# Connectors_1.net
KiCad netlist of a schematic drawn in Altium Designer
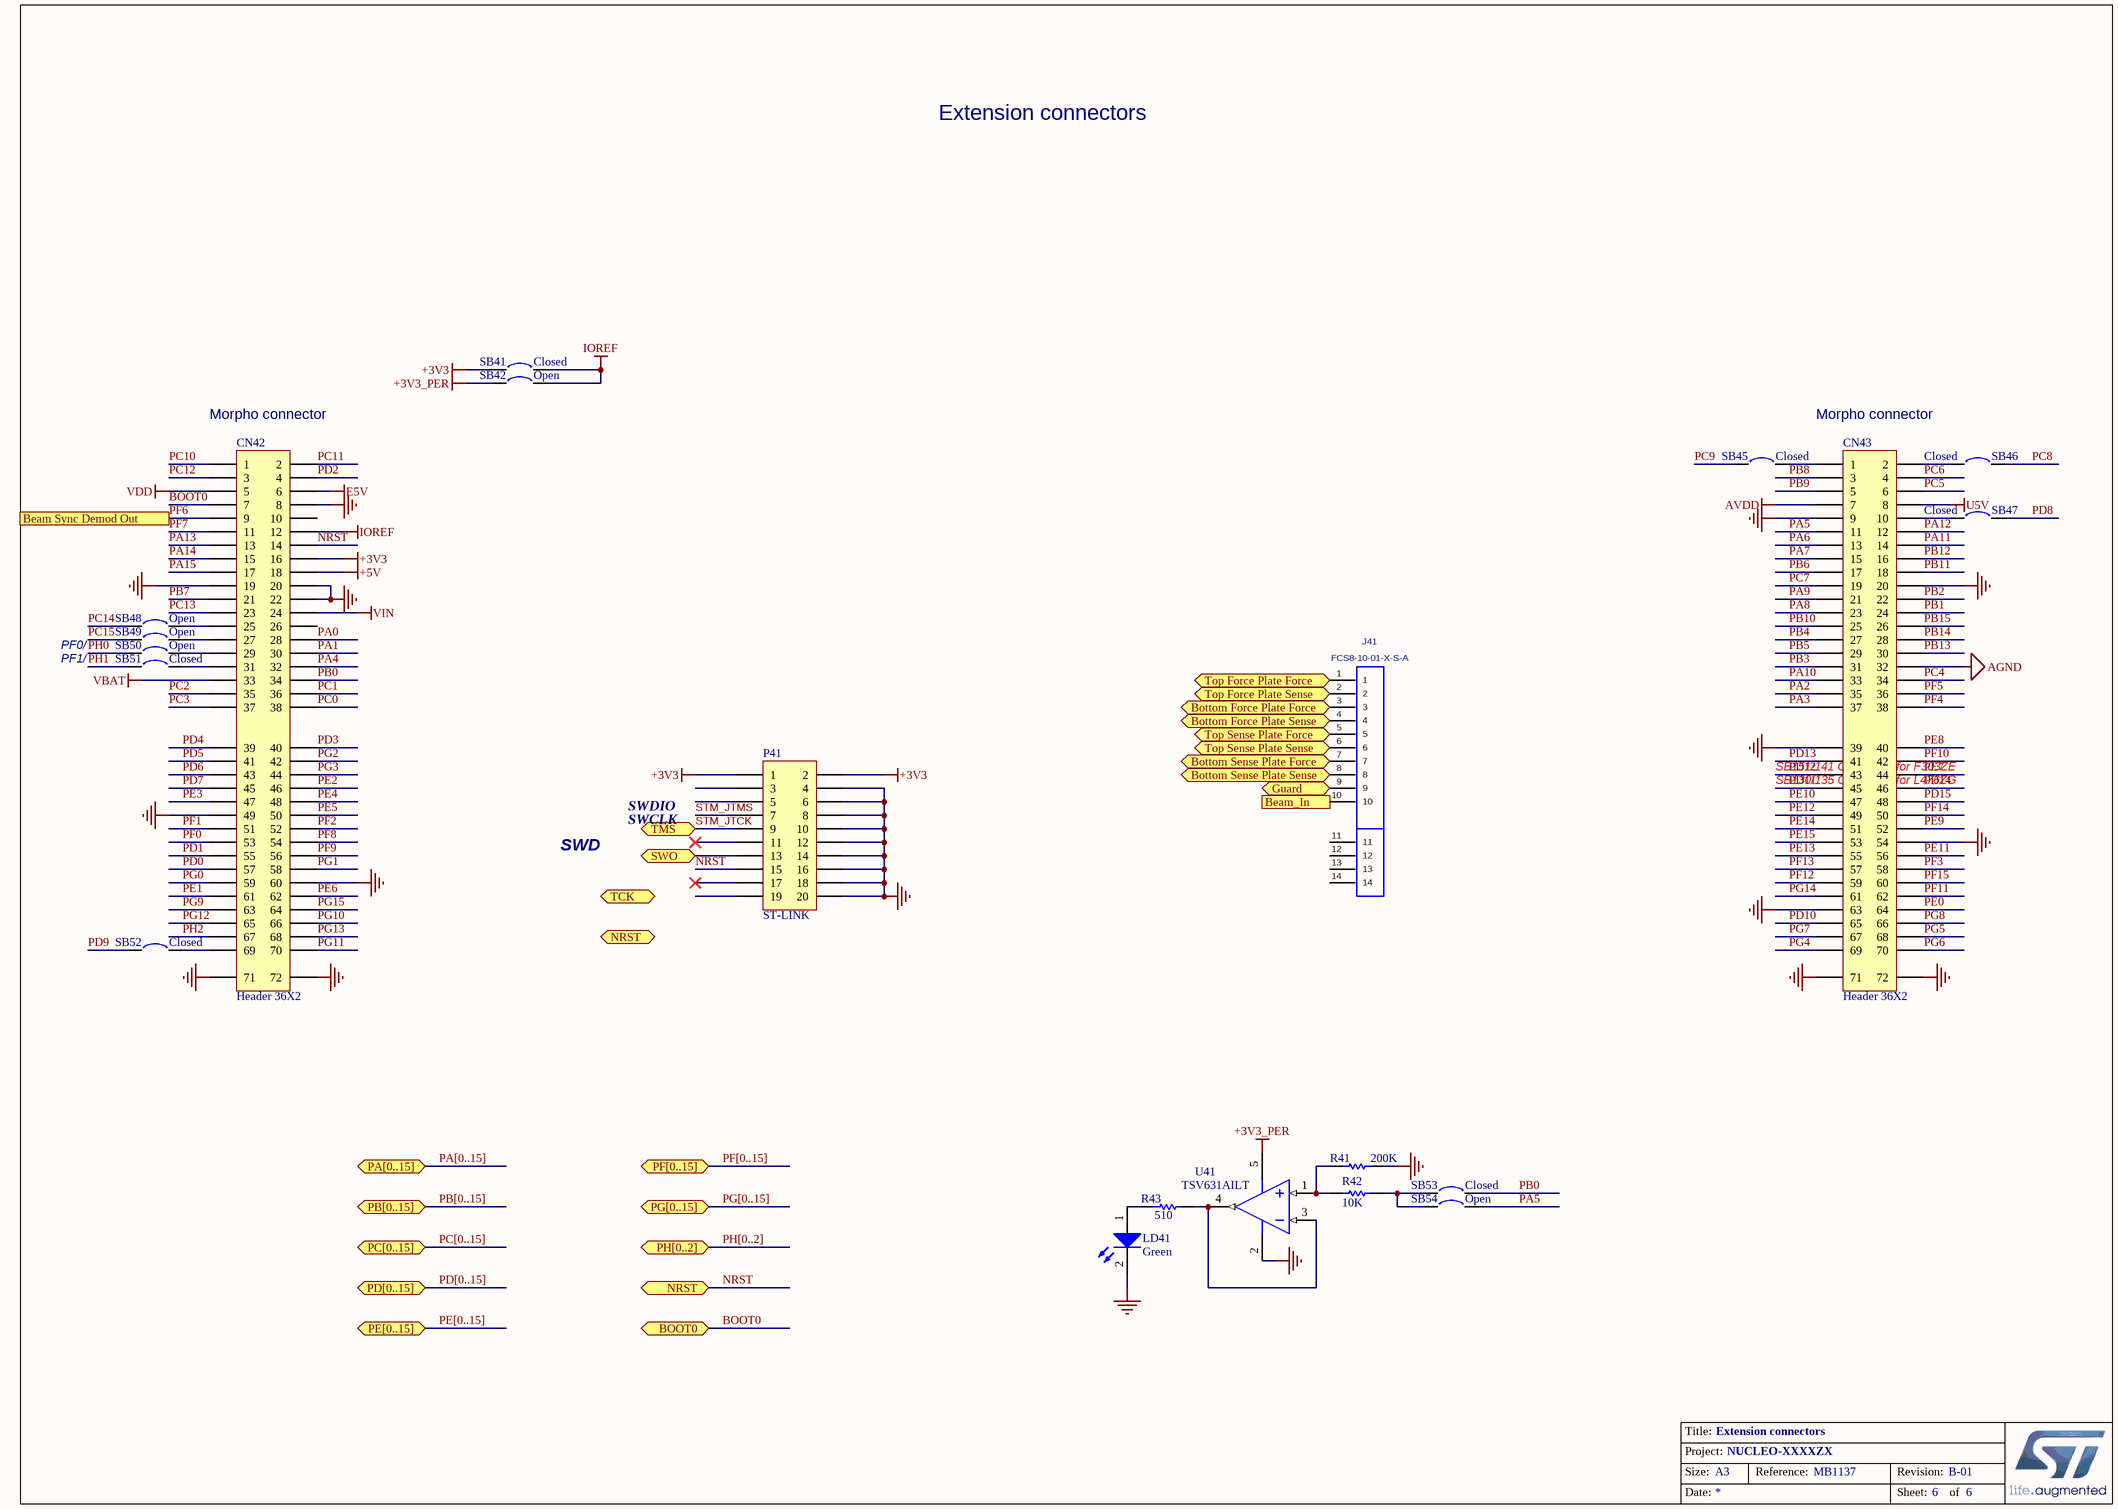
[diagram p0: Connectors_1.SchDoc]

(export (version "E")
  (design (tool "Eeschema 10.0.6"))
  (components
    (comp (ref "CN42")
      (value "Header 36X2")
      (footprint "HDR_2x36_2R54_V_M")
      (description "Header, 36-Pin, Dual row")
      (fields (field (name "PUBLISHER") "Altium Limited"))
      (libsource (lib "MB1137") (part "Header 36X2"))
    )
    (comp (ref "CN43")
      (value "Header 36X2")
      (footprint "HDR_2x36_2R54_V_M")
      (description "Header, 36-Pin, Dual row")
      (fields (field (name "PUBLISHER") "Altium Limited"))
      (libsource (lib "MB1137") (part "Header 36X2"))
    )
    (comp (ref "J41")
      (value "FCS8-10-01-X-S-A")
      (footprint "FCS8-10-01-X-S-A")
      (description "FCS8 Socket Assembly, 20-Pins, w/ Alignment Pins")
      (fields (field (name "MANUFACTURER") "SAMTEC") (field (name "CREATED") "31 NOV 2013 - WENDY XIN"))
      (libsource (lib "FCS8-10-01-X-S-A") (part "FCS8-10-01-X-S-A"))
    )
    (comp (ref "LD41")
      (value "Green")
      (footprint "0603D-G")
      (description "Typical RED, GREEN, YELLOW, AMBER GaAs LED")
      (fields (field (name "PUBLISHER") "Altium Limited"))
      (libsource (lib "Miscellaneous Devices") (part "LED2"))
    )
    (comp (ref "P41")
      (value "ST-LINK")
      (footprint "HDR2X10")
      (description "Header, 10-Pin, Dual row")
      (fields (field (name "PUBLISHER") "Altium Limited"))
      (libsource (lib "Miscellaneous Connectors") (part "Header 10X2"))
    )
    (comp (ref "R41")
      (value "200K")
      (footprint "0603R")
      (description "Resistor")
      (fields (field (name "PUBLISHER") "Altium Limited"))
      (libsource (lib "Miscellaneous Devices") (part "res1"))
    )
    (comp (ref "R42")
      (value "10K")
      (footprint "0603R")
      (description "Resistor")
      (fields (field (name "PUBLISHER") "Altium Limited"))
      (libsource (lib "Miscellaneous Devices") (part "res1"))
    )
    (comp (ref "R43")
      (value "510")
      (footprint "0603R")
      (description "Resistor")
      (fields (field (name "PUBLISHER") "Altium Limited"))
      (libsource (lib "Miscellaneous Devices") (part "Res1"))
    )
    (comp (ref "SB41")
      (value "Closed")
      (footprint "SB_0603")
      (description "Circuit Breaker")
      (fields (field (name "PUBLISHER") "Altium Limited"))
      (libsource (lib "MB1167") (part "Circuit Breaker_close"))
    )
    (comp (ref "SB42")
      (value "Open")
      (footprint "SB_0603")
      (description "Circuit Breaker")
      (fields (field (name "PUBLISHER") "Altium Limited"))
      (libsource (lib "MB1167") (part "Circuit Breaker"))
    )
    (comp (ref "SB45")
      (value "Closed")
      (footprint "SB_0603")
      (description "Circuit Breaker")
      (fields (field (name "PUBLISHER") "Altium Limited"))
      (libsource (lib "MB1167") (part "Circuit Breaker_close"))
    )
    (comp (ref "SB46")
      (value "Closed")
      (footprint "SB_0603")
      (description "Circuit Breaker")
      (fields (field (name "PUBLISHER") "Altium Limited"))
      (libsource (lib "") (part "Circuit Breaker_close_1"))
    )
    (comp (ref "SB47")
      (value "Closed")
      (footprint "SB_0603")
      (description "Circuit Breaker")
      (fields (field (name "PUBLISHER") "Altium Limited"))
      (libsource (lib "MB1167") (part "Circuit Breaker_close"))
    )
    (comp (ref "SB48")
      (value "Open")
      (footprint "SB_0603")
      (description "Circuit Breaker")
      (fields (field (name "PUBLISHER") "Altium Limited"))
      (libsource (lib "MB1167") (part "Circuit Breaker"))
    )
    (comp (ref "SB49")
      (value "Open")
      (footprint "SB_0603")
      (description "Circuit Breaker")
      (fields (field (name "PUBLISHER") "Altium Limited"))
      (libsource (lib "MB1167") (part "Circuit Breaker"))
    )
    (comp (ref "SB50")
      (value "Open")
      (footprint "SB_0603")
      (description "Circuit Breaker")
      (fields (field (name "PUBLISHER") "Altium Limited"))
      (libsource (lib "MB1167") (part "Circuit Breaker"))
    )
    (comp (ref "SB51")
      (value "Closed")
      (footprint "SB_0603")
      (description "Circuit Breaker")
      (fields (field (name "PUBLISHER") "Altium Limited"))
      (libsource (lib "MB1167") (part "Circuit Breaker_close"))
    )
    (comp (ref "SB52")
      (value "Closed")
      (footprint "SB_0603")
      (description "Circuit Breaker")
      (fields (field (name "PUBLISHER") "Altium Limited"))
      (libsource (lib "MB1167") (part "Circuit Breaker_close"))
    )
    (comp (ref "SB53")
      (value "Closed")
      (footprint "SB_0603")
      (description "Circuit Breaker")
      (fields (field (name "PUBLISHER") "Altium Limited"))
      (libsource (lib "") (part "Circuit Breaker_close_1"))
    )
    (comp (ref "SB54")
      (value "Open")
      (footprint "SB_0603")
      (description "Circuit Breaker")
      (fields (field (name "PUBLISHER") "Altium Limited"))
      (libsource (lib "MB1167") (part "Circuit Breaker"))
    )
    (comp (ref "U41")
      (value "TSV631AILT")
      (footprint "SOT-23-5L")
      (libsource (lib "MB988") (part "TSV631AILT"))
    )
  )
  (nets
    (net (code "1") (name "+3V3") (class "Default")
      (node (ref "CN42") (pin "16") (pinfunction "16_16") (pintype "passive"))
      (node (ref "P41") (pin "1") (pinfunction "1_1") (pintype "passive"))
      (node (ref "P41") (pin "2") (pinfunction "2_2") (pintype "passive"))
      (node (ref "SB41") (pin "1") (pinfunction "1_1") (pintype "passive"))
    )
    (net (code "2") (name "+3V3_PER") (class "Default")
      (node (ref "SB42") (pin "1") (pinfunction "1_1") (pintype "passive"))
      (node (ref "U41") (pin "5") (pinfunction "VCC_5") (pintype "power_in"))
    )
    (net (code "3") (name "+5V") (class "Default")
      (node (ref "CN42") (pin "18") (pinfunction "18_18") (pintype "passive"))
    )
    (net (code "4") (name "/BOOT0") (class "Default")
      (node (ref "CN42") (pin "7") (pinfunction "7_7") (pintype "passive"))
    )
    (net (code "5") (name "/Beam_In") (class "Default")
      (node (ref "J41") (pin "10") (pinfunction "10_10") (pintype "passive"))
    )
    (net (code "6") (name "/Bottom Force Plate Force") (class "Default")
      (node (ref "J41") (pin "3") (pinfunction "3_3") (pintype "passive"))
    )
    (net (code "7") (name "/Bottom Force Plate Sense") (class "Default")
      (node (ref "J41") (pin "4") (pinfunction "4_4") (pintype "passive"))
    )
    (net (code "8") (name "/Bottom Sense Plate Force") (class "Default")
      (node (ref "J41") (pin "7") (pinfunction "7_7") (pintype "passive"))
    )
    (net (code "9") (name "/Bottom Sense Plate Sense") (class "Default")
      (node (ref "J41") (pin "8") (pinfunction "8_8") (pintype "passive"))
    )
    (net (code "10") (name "/Guard") (class "Default")
      (node (ref "J41") (pin "9") (pinfunction "9_9") (pintype "passive"))
    )
    (net (code "11") (name "/NRST") (class "Default")
      (node (ref "CN42") (pin "14") (pinfunction "14_14") (pintype "passive"))
      (node (ref "P41") (pin "15") (pinfunction "15_15") (pintype "passive"))
    )
    (net (code "12") (name "/PA0") (class "Default")
      (node (ref "CN42") (pin "28") (pinfunction "28_28") (pintype "passive"))
    )
    (net (code "13") (name "/PA1") (class "Default")
      (node (ref "CN42") (pin "30") (pinfunction "30_30") (pintype "passive"))
    )
    (net (code "14") (name "/PA2") (class "Default")
      (node (ref "CN43") (pin "35") (pinfunction "35_35") (pintype "passive"))
    )
    (net (code "15") (name "/PA3") (class "Default")
      (node (ref "CN43") (pin "37") (pinfunction "37_37") (pintype "passive"))
    )
    (net (code "16") (name "/PA4") (class "Default")
      (node (ref "CN42") (pin "32") (pinfunction "32_32") (pintype "passive"))
    )
    (net (code "17") (name "/PA5") (class "Default")
      (node (ref "CN43") (pin "11") (pinfunction "11_11") (pintype "passive"))
      (node (ref "SB54") (pin "2") (pinfunction "2_2") (pintype "passive"))
    )
    (net (code "18") (name "/PA6") (class "Default")
      (node (ref "CN43") (pin "13") (pinfunction "13_13") (pintype "passive"))
    )
    (net (code "19") (name "/PA7") (class "Default")
      (node (ref "CN43") (pin "15") (pinfunction "15_15") (pintype "passive"))
    )
    (net (code "20") (name "/PA8") (class "Default")
      (node (ref "CN43") (pin "23") (pinfunction "23_23") (pintype "passive"))
    )
    (net (code "21") (name "/PA9") (class "Default")
      (node (ref "CN43") (pin "21") (pinfunction "21_21") (pintype "passive"))
    )
    (net (code "22") (name "/PA10") (class "Default")
      (node (ref "CN43") (pin "33") (pinfunction "33_33") (pintype "passive"))
    )
    (net (code "23") (name "/PA11") (class "Default")
      (node (ref "CN43") (pin "14") (pinfunction "14_14") (pintype "passive"))
    )
    (net (code "24") (name "/PA12") (class "Default")
      (node (ref "CN43") (pin "12") (pinfunction "12_12") (pintype "passive"))
    )
    (net (code "25") (name "/PA13") (class "Default")
      (node (ref "CN42") (pin "13") (pinfunction "13_13") (pintype "passive"))
    )
    (net (code "26") (name "/PA14") (class "Default")
      (node (ref "CN42") (pin "15") (pinfunction "15_15") (pintype "passive"))
    )
    (net (code "27") (name "/PA15") (class "Default")
      (node (ref "CN42") (pin "17") (pinfunction "17_17") (pintype "passive"))
    )
    (net (code "29") (name "/PB0") (class "Default")
      (node (ref "CN42") (pin "34") (pinfunction "34_34") (pintype "passive"))
      (node (ref "SB53") (pin "1") (pinfunction "1_1") (pintype "passive"))
    )
    (net (code "30") (name "/PB1") (class "Default")
      (node (ref "CN43") (pin "24") (pinfunction "24_24") (pintype "passive"))
    )
    (net (code "31") (name "/PB2") (class "Default")
      (node (ref "CN43") (pin "22") (pinfunction "22_22") (pintype "passive"))
    )
    (net (code "32") (name "/PB3") (class "Default")
      (node (ref "CN43") (pin "31") (pinfunction "31_31") (pintype "passive"))
    )
    (net (code "33") (name "/PB4") (class "Default")
      (node (ref "CN43") (pin "27") (pinfunction "27_27") (pintype "passive"))
    )
    (net (code "34") (name "/PB5") (class "Default")
      (node (ref "CN43") (pin "29") (pinfunction "29_29") (pintype "passive"))
    )
    (net (code "35") (name "/PB6") (class "Default")
      (node (ref "CN43") (pin "17") (pinfunction "17_17") (pintype "passive"))
    )
    (net (code "36") (name "/PB7") (class "Default")
      (node (ref "CN42") (pin "21") (pinfunction "21_21") (pintype "passive"))
    )
    (net (code "37") (name "/PB8") (class "Default")
      (node (ref "CN43") (pin "3") (pinfunction "3_3") (pintype "passive"))
    )
    (net (code "38") (name "/PB9") (class "Default")
      (node (ref "CN43") (pin "5") (pinfunction "5_5") (pintype "passive"))
    )
    (net (code "39") (name "/PB10") (class "Default")
      (node (ref "CN43") (pin "25") (pinfunction "25_25") (pintype "passive"))
    )
    (net (code "40") (name "/PB11") (class "Default")
      (node (ref "CN43") (pin "18") (pinfunction "18_18") (pintype "passive"))
    )
    (net (code "41") (name "/PB12") (class "Default")
      (node (ref "CN43") (pin "16") (pinfunction "16_16") (pintype "passive"))
    )
    (net (code "42") (name "/PB13") (class "Default")
      (node (ref "CN43") (pin "30") (pinfunction "30_30") (pintype "passive"))
    )
    (net (code "43") (name "/PB14") (class "Default")
      (node (ref "CN43") (pin "28") (pinfunction "28_28") (pintype "passive"))
    )
    (net (code "44") (name "/PB15") (class "Default")
      (node (ref "CN43") (pin "26") (pinfunction "26_26") (pintype "passive"))
    )
    (net (code "46") (name "/PC0") (class "Default")
      (node (ref "CN42") (pin "38") (pinfunction "38_38") (pintype "passive"))
    )
    (net (code "47") (name "/PC1") (class "Default")
      (node (ref "CN42") (pin "36") (pinfunction "36_36") (pintype "passive"))
    )
    (net (code "48") (name "/PC2") (class "Default")
      (node (ref "CN42") (pin "35") (pinfunction "35_35") (pintype "passive"))
    )
    (net (code "49") (name "/PC3") (class "Default")
      (node (ref "CN42") (pin "37") (pinfunction "37_37") (pintype "passive"))
    )
    (net (code "50") (name "/PC4") (class "Default")
      (node (ref "CN43") (pin "34") (pinfunction "34_34") (pintype "passive"))
    )
    (net (code "51") (name "/PC5") (class "Default")
      (node (ref "CN43") (pin "6") (pinfunction "6_6") (pintype "passive"))
    )
    (net (code "52") (name "/PC6") (class "Default")
      (node (ref "CN43") (pin "4") (pinfunction "4_4") (pintype "passive"))
    )
    (net (code "53") (name "/PC7") (class "Default")
      (node (ref "CN43") (pin "19") (pinfunction "19_19") (pintype "passive"))
    )
    (net (code "54") (name "/PC8") (class "Default")
      (node (ref "SB46") (pin "1") (pinfunction "1_1") (pintype "passive"))
    )
    (net (code "55") (name "/PC9") (class "Default")
      (node (ref "SB45") (pin "1") (pinfunction "1_1") (pintype "passive"))
    )
    (net (code "56") (name "/PC10") (class "Default")
      (node (ref "CN42") (pin "1") (pinfunction "1_1") (pintype "passive"))
    )
    (net (code "57") (name "/PC11") (class "Default")
      (node (ref "CN42") (pin "2") (pinfunction "2_2") (pintype "passive"))
    )
    (net (code "58") (name "/PC12") (class "Default")
      (node (ref "CN42") (pin "3") (pinfunction "3_3") (pintype "passive"))
    )
    (net (code "59") (name "/PC13") (class "Default")
      (node (ref "CN42") (pin "23") (pinfunction "23_23") (pintype "passive"))
    )
    (net (code "60") (name "/PC14") (class "Default")
      (node (ref "SB48") (pin "1") (pinfunction "1_1") (pintype "passive"))
    )
    (net (code "61") (name "/PC15") (class "Default")
      (node (ref "SB49") (pin "1") (pinfunction "1_1") (pintype "passive"))
    )
    (net (code "63") (name "/PD0") (class "Default")
      (node (ref "CN42") (pin "57") (pinfunction "57_57") (pintype "passive"))
    )
    (net (code "64") (name "/PD1") (class "Default")
      (node (ref "CN42") (pin "55") (pinfunction "55_55") (pintype "passive"))
    )
    (net (code "65") (name "/PD2") (class "Default")
      (node (ref "CN42") (pin "4") (pinfunction "4_4") (pintype "passive"))
    )
    (net (code "66") (name "/PD3") (class "Default")
      (node (ref "CN42") (pin "40") (pinfunction "40_40") (pintype "passive"))
    )
    (net (code "67") (name "/PD4") (class "Default")
      (node (ref "CN42") (pin "39") (pinfunction "39_39") (pintype "passive"))
    )
    (net (code "68") (name "/PD5") (class "Default")
      (node (ref "CN42") (pin "41") (pinfunction "41_41") (pintype "passive"))
    )
    (net (code "69") (name "/PD6") (class "Default")
      (node (ref "CN42") (pin "43") (pinfunction "43_43") (pintype "passive"))
    )
    (net (code "70") (name "/PD7") (class "Default")
      (node (ref "CN42") (pin "45") (pinfunction "45_45") (pintype "passive"))
    )
    (net (code "71") (name "/PD8") (class "Default")
      (node (ref "SB47") (pin "2") (pinfunction "2_2") (pintype "passive"))
    )
    (net (code "72") (name "/PD9") (class "Default")
      (node (ref "SB52") (pin "1") (pinfunction "1_1") (pintype "passive"))
    )
    (net (code "73") (name "/PD10") (class "Default")
      (node (ref "CN43") (pin "65") (pinfunction "65_65") (pintype "passive"))
    )
    (net (code "74") (name "/PD11") (class "Default")
      (node (ref "CN43") (pin "45") (pinfunction "45_45") (pintype "passive"))
    )
    (net (code "75") (name "/PD12") (class "Default")
      (node (ref "CN43") (pin "43") (pinfunction "43_43") (pintype "passive"))
    )
    (net (code "76") (name "/PD13") (class "Default")
      (node (ref "CN43") (pin "41") (pinfunction "41_41") (pintype "passive"))
    )
    (net (code "77") (name "/PD14") (class "Default")
      (node (ref "CN43") (pin "46") (pinfunction "46_46") (pintype "passive"))
    )
    (net (code "78") (name "/PD15") (class "Default")
      (node (ref "CN43") (pin "48") (pinfunction "48_48") (pintype "passive"))
    )
    (net (code "80") (name "/PE0") (class "Default")
      (node (ref "CN43") (pin "64") (pinfunction "64_64") (pintype "passive"))
    )
    (net (code "81") (name "/PE1") (class "Default")
      (node (ref "CN42") (pin "61") (pinfunction "61_61") (pintype "passive"))
    )
    (net (code "82") (name "/PE2") (class "Default")
      (node (ref "CN42") (pin "46") (pinfunction "46_46") (pintype "passive"))
    )
    (net (code "83") (name "/PE3") (class "Default")
      (node (ref "CN42") (pin "47") (pinfunction "47_47") (pintype "passive"))
    )
    (net (code "84") (name "/PE4") (class "Default")
      (node (ref "CN42") (pin "48") (pinfunction "48_48") (pintype "passive"))
    )
    (net (code "85") (name "/PE5") (class "Default")
      (node (ref "CN42") (pin "50") (pinfunction "50_50") (pintype "passive"))
    )
    (net (code "86") (name "/PE6") (class "Default")
      (node (ref "CN42") (pin "62") (pinfunction "62_62") (pintype "passive"))
    )
    (net (code "87") (name "/PE7") (class "Default")
      (node (ref "CN43") (pin "44") (pinfunction "44_44") (pintype "passive"))
    )
    (net (code "88") (name "/PE8") (class "Default")
      (node (ref "CN43") (pin "40") (pinfunction "40_40") (pintype "passive"))
    )
    (net (code "89") (name "/PE9") (class "Default")
      (node (ref "CN43") (pin "52") (pinfunction "52_52") (pintype "passive"))
    )
    (net (code "90") (name "/PE10") (class "Default")
      (node (ref "CN43") (pin "47") (pinfunction "47_47") (pintype "passive"))
    )
    (net (code "91") (name "/PE11") (class "Default")
      (node (ref "CN43") (pin "56") (pinfunction "56_56") (pintype "passive"))
    )
    (net (code "92") (name "/PE12") (class "Default")
      (node (ref "CN43") (pin "49") (pinfunction "49_49") (pintype "passive"))
    )
    (net (code "93") (name "/PE13") (class "Default")
      (node (ref "CN43") (pin "55") (pinfunction "55_55") (pintype "passive"))
    )
    (net (code "94") (name "/PE14") (class "Default")
      (node (ref "CN43") (pin "51") (pinfunction "51_51") (pintype "passive"))
    )
    (net (code "95") (name "/PE15") (class "Default")
      (node (ref "CN43") (pin "53") (pinfunction "53_53") (pintype "passive"))
    )
    (net (code "97") (name "/PF0") (class "Default")
      (node (ref "CN42") (pin "53") (pinfunction "53_53") (pintype "passive"))
    )
    (net (code "98") (name "/PF1") (class "Default")
      (node (ref "CN42") (pin "51") (pinfunction "51_51") (pintype "passive"))
    )
    (net (code "99") (name "/PF2") (class "Default")
      (node (ref "CN42") (pin "52") (pinfunction "52_52") (pintype "passive"))
    )
    (net (code "100") (name "/PF3") (class "Default")
      (node (ref "CN43") (pin "58") (pinfunction "58_58") (pintype "passive"))
    )
    (net (code "101") (name "/PF4") (class "Default")
      (node (ref "CN43") (pin "38") (pinfunction "38_38") (pintype "passive"))
    )
    (net (code "102") (name "/PF5") (class "Default")
      (node (ref "CN43") (pin "36") (pinfunction "36_36") (pintype "passive"))
    )
    (net (code "103") (name "/PF6") (class "Default")
      (node (ref "CN42") (pin "9") (pinfunction "9_9") (pintype "passive"))
    )
    (net (code "104") (name "/PF7") (class "Default")
      (node (ref "CN42") (pin "11") (pinfunction "11_11") (pintype "passive"))
    )
    (net (code "105") (name "/PF8") (class "Default")
      (node (ref "CN42") (pin "54") (pinfunction "54_54") (pintype "passive"))
    )
    (net (code "106") (name "/PF9") (class "Default")
      (node (ref "CN42") (pin "56") (pinfunction "56_56") (pintype "passive"))
    )
    (net (code "107") (name "/PF10") (class "Default")
      (node (ref "CN43") (pin "42") (pinfunction "42_42") (pintype "passive"))
    )
    (net (code "108") (name "/PF11") (class "Default")
      (node (ref "CN43") (pin "62") (pinfunction "62_62") (pintype "passive"))
    )
    (net (code "109") (name "/PF12") (class "Default")
      (node (ref "CN43") (pin "59") (pinfunction "59_59") (pintype "passive"))
    )
    (net (code "110") (name "/PF13") (class "Default")
      (node (ref "CN43") (pin "57") (pinfunction "57_57") (pintype "passive"))
    )
    (net (code "111") (name "/PF14") (class "Default")
      (node (ref "CN43") (pin "50") (pinfunction "50_50") (pintype "passive"))
    )
    (net (code "112") (name "/PF15") (class "Default")
      (node (ref "CN43") (pin "60") (pinfunction "60_60") (pintype "passive"))
    )
    (net (code "114") (name "/PG0") (class "Default")
      (node (ref "CN42") (pin "59") (pinfunction "59_59") (pintype "passive"))
    )
    (net (code "115") (name "/PG1") (class "Default")
      (node (ref "CN42") (pin "58") (pinfunction "58_58") (pintype "passive"))
    )
    (net (code "116") (name "/PG2") (class "Default")
      (node (ref "CN42") (pin "42") (pinfunction "42_42") (pintype "passive"))
    )
    (net (code "117") (name "/PG3") (class "Default")
      (node (ref "CN42") (pin "44") (pinfunction "44_44") (pintype "passive"))
    )
    (net (code "118") (name "/PG4") (class "Default")
      (node (ref "CN43") (pin "69") (pinfunction "69_69") (pintype "passive"))
    )
    (net (code "119") (name "/PG5") (class "Default")
      (node (ref "CN43") (pin "68") (pinfunction "68_68") (pintype "passive"))
    )
    (net (code "120") (name "/PG6") (class "Default")
      (node (ref "CN43") (pin "70") (pinfunction "70_70") (pintype "passive"))
    )
    (net (code "121") (name "/PG7") (class "Default")
      (node (ref "CN43") (pin "67") (pinfunction "67_67") (pintype "passive"))
    )
    (net (code "122") (name "/PG8") (class "Default")
      (node (ref "CN43") (pin "66") (pinfunction "66_66") (pintype "passive"))
    )
    (net (code "123") (name "/PG9") (class "Default")
      (node (ref "CN42") (pin "63") (pinfunction "63_63") (pintype "passive"))
    )
    (net (code "124") (name "/PG10") (class "Default")
      (node (ref "CN42") (pin "66") (pinfunction "66_66") (pintype "passive"))
    )
    (net (code "125") (name "/PG11") (class "Default")
      (node (ref "CN42") (pin "70") (pinfunction "70_70") (pintype "passive"))
    )
    (net (code "126") (name "/PG12") (class "Default")
      (node (ref "CN42") (pin "65") (pinfunction "65_65") (pintype "passive"))
    )
    (net (code "127") (name "/PG13") (class "Default")
      (node (ref "CN42") (pin "68") (pinfunction "68_68") (pintype "passive"))
    )
    (net (code "128") (name "/PG14") (class "Default")
      (node (ref "CN43") (pin "61") (pinfunction "61_61") (pintype "passive"))
    )
    (net (code "129") (name "/PG15") (class "Default")
      (node (ref "CN42") (pin "64") (pinfunction "64_64") (pintype "passive"))
    )
    (net (code "131") (name "/PH0") (class "Default")
      (node (ref "SB50") (pin "1") (pinfunction "1_1") (pintype "passive"))
    )
    (net (code "132") (name "/PH1") (class "Default")
      (node (ref "SB51") (pin "1") (pinfunction "1_1") (pintype "passive"))
    )
    (net (code "133") (name "/PH2") (class "Default")
      (node (ref "CN42") (pin "67") (pinfunction "67_67") (pintype "passive"))
    )
    (net (code "135") (name "/STM_JTCK") (class "Default")
      (node (ref "P41") (pin "9") (pinfunction "9_9") (pintype "passive"))
    )
    (net (code "136") (name "/STM_JTMS") (class "Default")
      (node (ref "P41") (pin "7") (pinfunction "7_7") (pintype "passive"))
    )
    (net (code "137") (name "/SWO") (class "Default")
      (node (ref "P41") (pin "13") (pinfunction "13_13") (pintype "passive"))
    )
    (net (code "139") (name "/Top Force Plate Force") (class "Default")
      (node (ref "J41") (pin "1") (pinfunction "1_1") (pintype "passive"))
    )
    (net (code "140") (name "/Top Force Plate Sense") (class "Default")
      (node (ref "J41") (pin "2") (pinfunction "2_2") (pintype "passive"))
    )
    (net (code "141") (name "/Top Sense Plate Force") (class "Default")
      (node (ref "J41") (pin "5") (pinfunction "5_5") (pintype "passive"))
    )
    (net (code "142") (name "/Top Sense Plate Sense") (class "Default")
      (node (ref "J41") (pin "6") (pinfunction "6_6") (pintype "passive"))
    )
    (net (code "143") (name "AGND") (class "Default")
      (node (ref "CN43") (pin "32") (pinfunction "32_32") (pintype "passive"))
    )
    (net (code "144") (name "AVDD") (class "Default")
      (node (ref "CN43") (pin "7") (pinfunction "7_7") (pintype "passive"))
    )
    (net (code "145") (name "E5V") (class "Default")
      (node (ref "CN42") (pin "6") (pinfunction "6_6") (pintype "passive"))
    )
    (net (code "146") (name "GND") (class "Default")
      (node (ref "CN42") (pin "19") (pinfunction "19_19") (pintype "passive"))
      (node (ref "CN42") (pin "20") (pinfunction "20_20") (pintype "passive"))
      (node (ref "CN42") (pin "22") (pinfunction "22_22") (pintype "passive"))
      (node (ref "CN42") (pin "49") (pinfunction "49_49") (pintype "passive"))
      (node (ref "CN42") (pin "60") (pinfunction "60_60") (pintype "passive"))
      (node (ref "CN42") (pin "71") (pinfunction "71_71") (pintype "passive"))
      (node (ref "CN42") (pin "72") (pinfunction "72_72") (pintype "passive"))
      (node (ref "CN42") (pin "8") (pinfunction "8_8") (pintype "passive"))
      (node (ref "CN43") (pin "20") (pinfunction "20_20") (pintype "passive"))
      (node (ref "CN43") (pin "39") (pinfunction "39_39") (pintype "passive"))
      (node (ref "CN43") (pin "54") (pinfunction "54_54") (pintype "passive"))
      (node (ref "CN43") (pin "63") (pinfunction "63_63") (pintype "passive"))
      (node (ref "CN43") (pin "71") (pinfunction "71_71") (pintype "passive"))
      (node (ref "CN43") (pin "72") (pinfunction "72_72") (pintype "passive"))
      (node (ref "CN43") (pin "9") (pinfunction "9_9") (pintype "passive"))
      (node (ref "LD41") (pin "2") (pinfunction "K_2") (pintype "passive"))
      (node (ref "P41") (pin "10") (pinfunction "10_10") (pintype "passive"))
      (node (ref "P41") (pin "12") (pinfunction "12_12") (pintype "passive"))
      (node (ref "P41") (pin "14") (pinfunction "14_14") (pintype "passive"))
      (node (ref "P41") (pin "16") (pinfunction "16_16") (pintype "passive"))
      (node (ref "P41") (pin "18") (pinfunction "18_18") (pintype "passive"))
      (node (ref "P41") (pin "20") (pinfunction "20_20") (pintype "passive"))
      (node (ref "P41") (pin "4") (pinfunction "4_4") (pintype "passive"))
      (node (ref "P41") (pin "6") (pinfunction "6_6") (pintype "passive"))
      (node (ref "P41") (pin "8") (pinfunction "8_8") (pintype "passive"))
      (node (ref "R41") (pin "2") (pinfunction "2_2") (pintype "passive"))
      (node (ref "U41") (pin "2") (pinfunction "VDD_2") (pintype "power_in"))
    )
    (net (code "147") (name "IOREF") (class "Default")
      (node (ref "CN42") (pin "12") (pinfunction "12_12") (pintype "passive"))
      (node (ref "SB41") (pin "2") (pinfunction "2_2") (pintype "passive"))
      (node (ref "SB42") (pin "2") (pinfunction "2_2") (pintype "passive"))
    )
    (net (code "148") (name "Net-(CN42-Pad25)") (class "Default")
      (node (ref "CN42") (pin "25") (pinfunction "25_25") (pintype "passive"))
      (node (ref "SB48") (pin "2") (pinfunction "2_2") (pintype "passive"))
    )
    (net (code "149") (name "Net-(CN42-Pad27)") (class "Default")
      (node (ref "CN42") (pin "27") (pinfunction "27_27") (pintype "passive"))
      (node (ref "SB49") (pin "2") (pinfunction "2_2") (pintype "passive"))
    )
    (net (code "150") (name "Net-(CN42-Pad29)") (class "Default")
      (node (ref "CN42") (pin "29") (pinfunction "29_29") (pintype "passive"))
      (node (ref "SB50") (pin "2") (pinfunction "2_2") (pintype "passive"))
    )
    (net (code "151") (name "Net-(CN42-Pad31)") (class "Default")
      (node (ref "CN42") (pin "31") (pinfunction "31_31") (pintype "passive"))
      (node (ref "SB51") (pin "2") (pinfunction "2_2") (pintype "passive"))
    )
    (net (code "152") (name "Net-(CN42-Pad69)") (class "Default")
      (node (ref "CN42") (pin "69") (pinfunction "69_69") (pintype "passive"))
      (node (ref "SB52") (pin "2") (pinfunction "2_2") (pintype "passive"))
    )
    (net (code "153") (name "Net-(CN43-Pad1)") (class "Default")
      (node (ref "CN43") (pin "1") (pinfunction "1_1") (pintype "passive"))
      (node (ref "SB45") (pin "2") (pinfunction "2_2") (pintype "passive"))
    )
    (net (code "154") (name "Net-(CN43-Pad2)") (class "Default")
      (node (ref "CN43") (pin "2") (pinfunction "2_2") (pintype "passive"))
      (node (ref "SB46") (pin "2") (pinfunction "2_2") (pintype "passive"))
    )
    (net (code "155") (name "Net-(CN43-Pad10)") (class "Default")
      (node (ref "CN43") (pin "10") (pinfunction "10_10") (pintype "passive"))
      (node (ref "SB47") (pin "1") (pinfunction "1_1") (pintype "passive"))
    )
    (net (code "156") (name "Net-(LD41-A)") (class "Default")
      (node (ref "LD41") (pin "1") (pinfunction "A_1") (pintype "passive"))
      (node (ref "R43") (pin "2") (pinfunction "2_2") (pintype "passive"))
    )
    (net (code "157") (name "Net-(R42-Pad2)") (class "Default")
      (node (ref "R42") (pin "2") (pinfunction "2_2") (pintype "passive"))
      (node (ref "SB53") (pin "2") (pinfunction "2_2") (pintype "passive"))
      (node (ref "SB54") (pin "1") (pinfunction "1_1") (pintype "passive"))
    )
    (net (code "158") (name "Net-(U41-IN+)") (class "Default")
      (node (ref "R41") (pin "1") (pinfunction "1_1") (pintype "passive"))
      (node (ref "R42") (pin "1") (pinfunction "1_1") (pintype "passive"))
      (node (ref "U41") (pin "1") (pinfunction "IN+_1") (pintype "input"))
    )
    (net (code "159") (name "Net-(U41-IN-)") (class "Default")
      (node (ref "R43") (pin "1") (pinfunction "1_1") (pintype "passive"))
      (node (ref "U41") (pin "3") (pinfunction "IN-_3") (pintype "input"))
      (node (ref "U41") (pin "4") (pinfunction "OUT_4") (pintype "output"))
    )
    (net (code "160") (name "U5V") (class "Default")
      (node (ref "CN43") (pin "8") (pinfunction "8_8") (pintype "passive"))
    )
    (net (code "161") (name "VBAT") (class "Default")
      (node (ref "CN42") (pin "33") (pinfunction "33_33") (pintype "passive"))
    )
    (net (code "162") (name "VDD") (class "Default")
      (node (ref "CN42") (pin "5") (pinfunction "5_5") (pintype "passive"))
    )
    (net (code "163") (name "VIN") (class "Default")
      (node (ref "CN42") (pin "24") (pinfunction "24_24") (pintype "passive"))
    )
    (net (code "164") (name "unconnected-(CN42-Pad10)") (class "Default")
      (node (ref "CN42") (pin "10") (pinfunction "10_10") (pintype "passive"))
    )
    (net (code "165") (name "unconnected-(CN42-Pad26)") (class "Default")
      (node (ref "CN42") (pin "26") (pinfunction "26_26") (pintype "passive"))
    )
    (net (code "166") (name "unconnected-(J41-Pad11)") (class "Default")
      (node (ref "J41") (pin "11") (pinfunction "11_11") (pintype "passive"))
    )
    (net (code "167") (name "unconnected-(J41-Pad12)") (class "Default")
      (node (ref "J41") (pin "12") (pinfunction "12_12") (pintype "passive"))
    )
    (net (code "168") (name "unconnected-(J41-Pad13)") (class "Default")
      (node (ref "J41") (pin "13") (pinfunction "13_13") (pintype "passive"))
    )
    (net (code "169") (name "unconnected-(J41-Pad14)") (class "Default")
      (node (ref "J41") (pin "14") (pinfunction "14_14") (pintype "passive"))
    )
    (net (code "170") (name "unconnected-(P41-Pad3)") (class "Default")
      (node (ref "P41") (pin "3") (pinfunction "3_3") (pintype "passive"))
    )
    (net (code "171") (name "unconnected-(P41-Pad5)") (class "Default")
      (node (ref "P41") (pin "5") (pinfunction "5_5") (pintype "passive"))
    )
    (net (code "172") (name "unconnected-(P41-Pad11)") (class "Default")
      (node (ref "P41") (pin "11") (pinfunction "11_11") (pintype "passive+no_connect"))
    )
    (net (code "173") (name "unconnected-(P41-Pad17)") (class "Default")
      (node (ref "P41") (pin "17") (pinfunction "17_17") (pintype "passive+no_connect"))
    )
    (net (code "174") (name "unconnected-(P41-Pad19)") (class "Default")
      (node (ref "P41") (pin "19") (pinfunction "19_19") (pintype "passive"))
    )
  )
)
